# LM62.net
KiCad netlist of a schematic drawn in Altium Designer
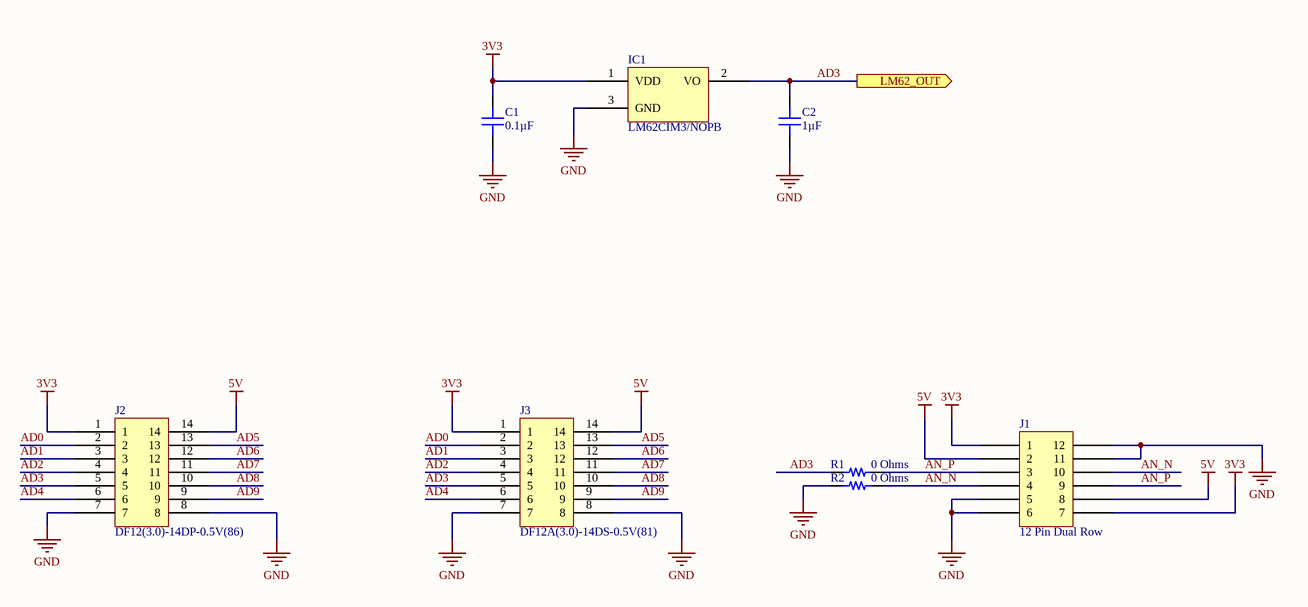
[diagram p0: LM62.SchDoc]

(export (version "E")
  (design (tool "Eeschema 10.0.6"))
  (components
    (comp (ref "C1")
      (value "0.1µF")
      (footprint "CAP 0603_1608")
      (description "CAP CER 0.1UF 16V Y5V 0603")
      (fields (field (name "PART NUMBER") "CC0603ZRY5V7BB104") (field (name "MANUFACTURER") "Yageo"))
      (libsource (lib "altiumlibrary.com") (part "Capacitor"))
    )
    (comp (ref "C2")
      (value "1µF")
      (footprint "CAP 0603_1608")
      (description "CAP CER 1UF 25V X5R 0603")
      (fields (field (name "PART NUMBER") "CC0603KRX5R8BB105") (field (name "MANUFACTURER") "Yageo"))
      (libsource (lib "altiumlibrary.com") (part "Capacitor"))
    )
    (comp (ref "IC1")
      (value "LM62CIM3/NOPB")
      (footprint "TI SOT-23-3 DBZ")
      (description "SENSOR ANALOG 0C-90C SOT23-3")
      (fields (field (name "MANUFACTURER") "Texas Instruments"))
      (libsource (lib "altiumlibrary.com") (part "TI LM62"))
    )
    (comp (ref "J1")
      (value "12 Pin Dual Row")
      (footprint "TE 5650118-3 Card Edge")
      (libsource (lib "CelestialUseful") (part "12 Pin Dual Row"))
    )
    (comp (ref "J2")
      (value "DF12(3.0)-14DP-0.5V(86)")
      (footprint "HIROSE DF12 3.0-14DP-0.5V 86")
      (description "CONN HDR 14POS SMD GOLD")
      (fields (field (name "MANUFACTURER") "Hirose Electric Co Ltd"))
      (libsource (lib "altiumlibrary.com") (part "14 Pin Dual Row"))
    )
    (comp (ref "J3")
      (value "DF12A(3.0)-14DS-0.5V(81)")
      (footprint "HIROSE DF12A 3.0-14DS-0.5V 81")
      (description "CONN RCPT 14POS SMD GOLD")
      (fields (field (name "MANUFACTURER") "Hirose Electric Co Ltd"))
      (libsource (lib "altiumlibrary.com") (part "14 Pin Dual Row"))
    )
    (comp (ref "R1")
      (value "0 Ohms")
      (footprint "RES 0603_1608")
      (description "RES SMD 0 OHM JUMPER 1/10W 0603")
      (fields
        (field (name "PART NUMBER") "ERJ-3GEY0R00V")
        (field (name "MANUFACTURER") "Panasonic Electronic Components")
      )
      (libsource (lib "altiumlibrary.com") (part "Resistor"))
    )
    (comp (ref "R2")
      (value "0 Ohms")
      (footprint "RES 0603_1608")
      (description "RES SMD 0 OHM JUMPER 1/10W 0603")
      (fields
        (field (name "PART NUMBER") "ERJ-3GEY0R00V")
        (field (name "MANUFACTURER") "Panasonic Electronic Components")
      )
      (libsource (lib "altiumlibrary.com") (part "Resistor"))
    )
  )
  (nets
    (net (code "1") (name "/AD0") (class "Default")
      (node (ref "J2") (pin "2") (pinfunction "2_2") (pintype "passive"))
      (node (ref "J3") (pin "2") (pinfunction "2_2") (pintype "passive"))
    )
    (net (code "2") (name "/AD1") (class "Default")
      (node (ref "J2") (pin "3") (pinfunction "3_3") (pintype "passive"))
      (node (ref "J3") (pin "3") (pinfunction "3_3") (pintype "passive"))
    )
    (net (code "3") (name "/AD2") (class "Default")
      (node (ref "J2") (pin "4") (pinfunction "4_4") (pintype "passive"))
      (node (ref "J3") (pin "4") (pinfunction "4_4") (pintype "passive"))
    )
    (net (code "4") (name "/AD3") (class "Default")
      (node (ref "C2") (pin "2") (pinfunction "2_2") (pintype "passive"))
      (node (ref "IC1") (pin "2") (pinfunction "VO_2") (pintype "passive"))
      (node (ref "J2") (pin "5") (pinfunction "5_5") (pintype "passive"))
      (node (ref "J3") (pin "5") (pinfunction "5_5") (pintype "passive"))
      (node (ref "R1") (pin "1") (pinfunction "1_1") (pintype "passive"))
    )
    (net (code "5") (name "/AD4") (class "Default")
      (node (ref "J2") (pin "6") (pinfunction "6_6") (pintype "passive"))
      (node (ref "J3") (pin "6") (pinfunction "6_6") (pintype "passive"))
    )
    (net (code "6") (name "/AD5") (class "Default")
      (node (ref "J2") (pin "13") (pinfunction "13_13") (pintype "passive"))
      (node (ref "J3") (pin "13") (pinfunction "13_13") (pintype "passive"))
    )
    (net (code "7") (name "/AD6") (class "Default")
      (node (ref "J2") (pin "12") (pinfunction "12_12") (pintype "passive"))
      (node (ref "J3") (pin "12") (pinfunction "12_12") (pintype "passive"))
    )
    (net (code "8") (name "/AD7") (class "Default")
      (node (ref "J2") (pin "11") (pinfunction "11_11") (pintype "passive"))
      (node (ref "J3") (pin "11") (pinfunction "11_11") (pintype "passive"))
    )
    (net (code "9") (name "/AD8") (class "Default")
      (node (ref "J2") (pin "10") (pinfunction "10_10") (pintype "passive"))
      (node (ref "J3") (pin "10") (pinfunction "10_10") (pintype "passive"))
    )
    (net (code "10") (name "/AD9") (class "Default")
      (node (ref "J2") (pin "9") (pinfunction "9_9") (pintype "passive"))
      (node (ref "J3") (pin "9") (pinfunction "9_9") (pintype "passive"))
    )
    (net (code "11") (name "/AN_N") (class "Default")
      (node (ref "J1") (pin "10") (pinfunction "10_10") (pintype "passive"))
      (node (ref "J1") (pin "4") (pinfunction "4_4") (pintype "passive"))
      (node (ref "R2") (pin "2") (pinfunction "2_2") (pintype "passive"))
    )
    (net (code "12") (name "/AN_P") (class "Default")
      (node (ref "J1") (pin "3") (pinfunction "3_3") (pintype "passive"))
      (node (ref "J1") (pin "9") (pinfunction "9_9") (pintype "passive"))
      (node (ref "R1") (pin "2") (pinfunction "2_2") (pintype "passive"))
    )
    (net (code "13") (name "3V3") (class "Default")
      (node (ref "C1") (pin "1") (pinfunction "1_1") (pintype "passive"))
      (node (ref "IC1") (pin "1") (pinfunction "VDD_1") (pintype "passive"))
      (node (ref "J1") (pin "1") (pinfunction "1_1") (pintype "passive"))
      (node (ref "J1") (pin "7") (pinfunction "7_7") (pintype "passive"))
      (node (ref "J2") (pin "1") (pinfunction "1_1") (pintype "passive"))
      (node (ref "J3") (pin "1") (pinfunction "1_1") (pintype "passive"))
    )
    (net (code "14") (name "5V") (class "Default")
      (node (ref "J1") (pin "2") (pinfunction "2_2") (pintype "passive"))
      (node (ref "J1") (pin "8") (pinfunction "8_8") (pintype "passive"))
      (node (ref "J2") (pin "14") (pinfunction "14_14") (pintype "passive"))
      (node (ref "J3") (pin "14") (pinfunction "14_14") (pintype "passive"))
    )
    (net (code "15") (name "GND") (class "Default")
      (node (ref "C1") (pin "2") (pinfunction "2_2") (pintype "passive"))
      (node (ref "C2") (pin "1") (pinfunction "1_1") (pintype "passive"))
      (node (ref "IC1") (pin "3") (pinfunction "GND_3") (pintype "passive"))
      (node (ref "J1") (pin "11") (pinfunction "11_11") (pintype "passive"))
      (node (ref "J1") (pin "12") (pinfunction "12_12") (pintype "passive"))
      (node (ref "J1") (pin "5") (pinfunction "5_5") (pintype "passive"))
      (node (ref "J1") (pin "6") (pinfunction "6_6") (pintype "passive"))
      (node (ref "J2") (pin "7") (pinfunction "7_7") (pintype "passive"))
      (node (ref "J2") (pin "8") (pinfunction "8_8") (pintype "passive"))
      (node (ref "J3") (pin "7") (pinfunction "7_7") (pintype "passive"))
      (node (ref "J3") (pin "8") (pinfunction "8_8") (pintype "passive"))
      (node (ref "R2") (pin "1") (pinfunction "1_1") (pintype "passive"))
    )
  )
)
